# Sheet1.net
KiCad netlist of a schematic drawn in Altium Designer
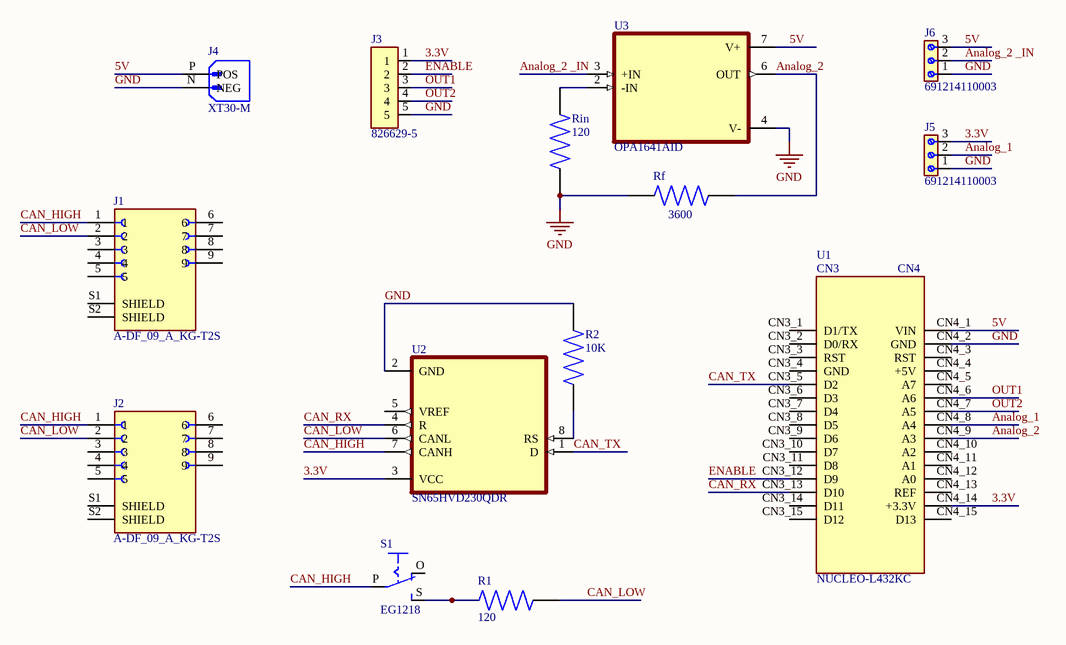
[diagram p0: Sheet1.SchDoc]

(export (version "E")
  (design (tool "Eeschema 10.0.6"))
  (components
    (comp (ref "J1")
      (value "A-DF_09_A_KG-T2S")
      (footprint "ASSMANN_A-DF_09_A_KG-T2S")
      (description "9 Position D-Sub Receptacle, Female Sockets Connector")
      (fields (field (name "MF") "Assmann WSW") (field (name "MP") "A-DF 09 A/KG-T2S"))
      (libsource (lib "A-DF_09_A_KG-T2S") (part "A-DF_09_A_KG-T2S"))
    )
    (comp (ref "J2")
      (value "A-DF_09_A_KG-T2S")
      (footprint "ASSMANN_A-DF_09_A_KG-T2S")
      (description "9 Position D-Sub Receptacle, Female Sockets Connector")
      (fields (field (name "MF") "Assmann WSW") (field (name "MP") "A-DF 09 A/KG-T2S"))
      (libsource (lib "A-DF_09_A_KG-T2S") (part "A-DF_09_A_KG-T2S"))
    )
    (comp (ref "J3")
      (value "826629-5")
      (footprint "TE_826629-5")
      (description "Board-To-Board Connector, AMPMODU MOD II Series, Through Hole, Header, 5, 2.54 mm")
      (fields (field (name "MF") "TE Connectivity"))
      (libsource (lib "826629-5") (part "826629-5"))
    )
    (comp (ref "J4")
      (value "XT30-M")
      (footprint "AMASS_XT60-M")
      (description "Plug; DC supply; XT60; male; PIN: 2; for cable; soldered; 30A; 500V")
      (fields (field (name "MP") "XT60-M") (field (name "MF") "AMASS"))
      (libsource (lib "XT30-M") (part "XT30-M"))
    )
    (comp (ref "J5")
      (value "691214110003")
      (footprint "691214110003")
      (description "PCB Terminal Block [WÃ¼rth Elektronik] 691214110003 PCB Terminal Block")
      (fields (field (name "MF") "Wurth Electronics"))
      (libsource (lib "691214110003") (part "691214110003"))
    )
    (comp (ref "J6")
      (value "691214110003")
      (footprint "691214110003")
      (description "PCB Terminal Block [WÃ¼rth Elektronik] 691214110003 PCB Terminal Block")
      (fields (field (name "MF") "Wurth Electronics"))
      (libsource (lib "691214110003") (part "691214110003"))
    )
    (comp (ref "R1")
      (value "120")
      (footprint "RESC3216X65N")
      (fields (field (name "MP") "KTR18EZPF9530"))
      (libsource (lib "KTR18EZPF9530") (part "KTR18EZPF9530"))
    )
    (comp (ref "R2")
      (value "10K")
      (footprint "RESC3216X65N")
      (fields (field (name "MP") "KTR18EZPF9530"))
      (libsource (lib "KTR18EZPF9530") (part "KTR18EZPF9530"))
    )
    (comp (ref "Rf")
      (value "3600")
      (footprint "RESC3216X65N")
      (fields (field (name "MP") "KTR18EZPF9530"))
      (libsource (lib "KTR18EZPF9530") (part "KTR18EZPF9530"))
    )
    (comp (ref "Rin")
      (value "120")
      (footprint "RESC3216X65N")
      (fields (field (name "MP") "KTR18EZPF9530"))
      (libsource (lib "KTR18EZPF9530") (part "KTR18EZPF9530"))
    )
    (comp (ref "S1") (value "EG1218") (footprint "EG1218:EG1218") (libsource (lib "EG1218") (part "EG1218")))
    (comp (ref "U1")
      (value "NUCLEO-L432KC")
      (footprint "MODULE_NUCLEO-L432KC")
      (description "STM32 Nucleo-32 development board with STM32L432KC MCU, supports Arduino connectivity")
      (libsource (lib "NUCLEO-L432KC") (part "NUCLEO-L432KC"))
    )
    (comp (ref "U2")
      (value "SN65HVD230QDR")
      (footprint "SOIC127P599X175-8N")
      (description "3.3-V CAN Transceiver with Standby Mode 8-SOIC -40 to 125")
      (fields (field (name "MF") "Texas Instruments"))
      (libsource (lib "SN65HVD230QDR") (part "SN65HVD230QDR"))
    )
    (comp (ref "U3")
      (value "OPA1641AID")
      (footprint "SOIC127P599X175-8N")
      (description "Single Sound-Plus High-Performance, JFET-Input Audio OpAmps 8-SOIC -40 to 85")
      (fields (field (name "MF") "Texas Instruments") (field (name "DIGI-KEY_PART_NUMBER") "296-48624-2-ND"))
      (libsource (lib "OPA1641AID") (part "OPA1641AID"))
    )
  )
  (nets
    (net (code "1") (name "/3.3V") (class "Default")
      (node (ref "J3") (pin "1") (pinfunction "1_1") (pintype "passive"))
      (node (ref "J5") (pin "3") (pinfunction "3_3") (pintype "passive"))
      (node (ref "U1") (pin "CN4_14") (pinfunction "+3.3V_CN4_14") (pintype "power_in"))
      (node (ref "U2") (pin "3") (pinfunction "VCC_3") (pintype "power_in"))
    )
    (net (code "2") (name "/5V") (class "Default")
      (node (ref "J4") (pin "P") (pinfunction "POS_P") (pintype "passive"))
      (node (ref "J6") (pin "3") (pinfunction "3_3") (pintype "passive"))
      (node (ref "U1") (pin "CN4_1") (pinfunction "VIN_CN4_1") (pintype "power_in"))
      (node (ref "U3") (pin "7") (pinfunction "V+_7") (pintype "power_in"))
    )
    (net (code "3") (name "/Analog_1") (class "Default")
      (node (ref "J5") (pin "2") (pinfunction "2_2") (pintype "passive"))
      (node (ref "U1") (pin "CN4_8") (pinfunction "A4_CN4_8") (pintype "passive"))
    )
    (net (code "4") (name "/Analog_2") (class "Default")
      (node (ref "Rf") (pin "1") (pinfunction "1_1") (pintype "passive"))
      (node (ref "U1") (pin "CN4_9") (pinfunction "A3_CN4_9") (pintype "passive"))
      (node (ref "U3") (pin "6") (pinfunction "OUT_6") (pintype "output"))
    )
    (net (code "5") (name "/Analog_2 _IN") (class "Default")
      (node (ref "J6") (pin "2") (pinfunction "2_2") (pintype "passive"))
      (node (ref "U3") (pin "3") (pinfunction "+IN_3") (pintype "input"))
    )
    (net (code "6") (name "/CAN_HIGH") (class "Default")
      (node (ref "J1") (pin "1") (pinfunction "1_1") (pintype "passive"))
      (node (ref "J2") (pin "1") (pinfunction "1_1") (pintype "passive"))
      (node (ref "S1") (pin "P") (pinfunction "P_P") (pintype "passive"))
      (node (ref "U2") (pin "7") (pinfunction "CANH_7") (pintype "output"))
    )
    (net (code "7") (name "/CAN_LOW") (class "Default")
      (node (ref "J1") (pin "2") (pinfunction "2_2") (pintype "passive"))
      (node (ref "J2") (pin "2") (pinfunction "2_2") (pintype "passive"))
      (node (ref "R1") (pin "2") (pinfunction "2_2") (pintype "passive"))
      (node (ref "U2") (pin "6") (pinfunction "CANL_6") (pintype "output"))
    )
    (net (code "8") (name "/CAN_RX") (class "Default")
      (node (ref "U1") (pin "CN3_13") (pinfunction "D10_CN3_13") (pintype "passive"))
      (node (ref "U2") (pin "4") (pinfunction "R_4") (pintype "output"))
    )
    (net (code "9") (name "/CAN_TX") (class "Default")
      (node (ref "U1") (pin "CN3_5") (pinfunction "D2_CN3_5") (pintype "power_in"))
      (node (ref "U2") (pin "1") (pinfunction "D_1") (pintype "input"))
    )
    (net (code "10") (name "/ENABLE") (class "Default")
      (node (ref "J3") (pin "2") (pinfunction "2_2") (pintype "passive"))
      (node (ref "U1") (pin "CN3_12") (pinfunction "D9_CN3_12") (pintype "power_in"))
    )
    (net (code "11") (name "/OUT1") (class "Default")
      (node (ref "J3") (pin "3") (pinfunction "3_3") (pintype "passive"))
      (node (ref "U1") (pin "CN4_6") (pinfunction "A6_CN4_6") (pintype "passive"))
    )
    (net (code "12") (name "/OUT2") (class "Default")
      (node (ref "J3") (pin "4") (pinfunction "4_4") (pintype "passive"))
      (node (ref "U1") (pin "CN4_7") (pinfunction "A5_CN4_7") (pintype "passive"))
    )
    (net (code "13") (name "GND") (class "Default")
      (node (ref "J3") (pin "5") (pinfunction "5_5") (pintype "passive"))
      (node (ref "J4") (pin "N") (pinfunction "NEG_N") (pintype "passive"))
      (node (ref "J5") (pin "1") (pinfunction "1_1") (pintype "passive"))
      (node (ref "J6") (pin "1") (pinfunction "1_1") (pintype "passive"))
      (node (ref "R2") (pin "2") (pinfunction "2_2") (pintype "passive"))
      (node (ref "Rf") (pin "2") (pinfunction "2_2") (pintype "passive"))
      (node (ref "Rin") (pin "1") (pinfunction "1_1") (pintype "passive"))
      (node (ref "U1") (pin "CN4_2") (pinfunction "GND_CN4_2") (pintype "power_in"))
      (node (ref "U2") (pin "2") (pinfunction "GND_2") (pintype "power_in"))
      (node (ref "U3") (pin "4") (pinfunction "V-_4") (pintype "power_in"))
    )
    (net (code "14") (name "Net-(R1-Pad1)") (class "Default")
      (node (ref "R1") (pin "1") (pinfunction "1_1") (pintype "passive"))
      (node (ref "S1") (pin "S") (pinfunction "S_S") (pintype "passive"))
    )
    (net (code "15") (name "Net-(U2-RS)") (class "Default")
      (node (ref "R2") (pin "1") (pinfunction "1_1") (pintype "passive"))
      (node (ref "U2") (pin "8") (pinfunction "RS_8") (pintype "input"))
    )
    (net (code "16") (name "Net-(U3--IN)") (class "Default")
      (node (ref "Rin") (pin "2") (pinfunction "2_2") (pintype "passive"))
      (node (ref "U3") (pin "2") (pinfunction "-IN_2") (pintype "input"))
    )
    (net (code "17") (name "unconnected-(J1-Pad3)") (class "Default")
      (node (ref "J1") (pin "3") (pinfunction "3_3") (pintype "passive"))
    )
    (net (code "18") (name "unconnected-(J1-Pad4)") (class "Default")
      (node (ref "J1") (pin "4") (pinfunction "4_4") (pintype "passive"))
    )
    (net (code "19") (name "unconnected-(J1-Pad5)") (class "Default")
      (node (ref "J1") (pin "5") (pinfunction "5_5") (pintype "passive"))
    )
    (net (code "20") (name "unconnected-(J1-Pad6)") (class "Default")
      (node (ref "J1") (pin "6") (pinfunction "6_6") (pintype "passive"))
    )
    (net (code "21") (name "unconnected-(J1-Pad7)") (class "Default")
      (node (ref "J1") (pin "7") (pinfunction "7_7") (pintype "passive"))
    )
    (net (code "22") (name "unconnected-(J1-Pad8)") (class "Default")
      (node (ref "J1") (pin "8") (pinfunction "8_8") (pintype "passive"))
    )
    (net (code "23") (name "unconnected-(J1-Pad9)") (class "Default")
      (node (ref "J1") (pin "9") (pinfunction "9_9") (pintype "passive"))
    )
    (net (code "24") (name "unconnected-(J1-SHIELD-PadS1)") (class "Default")
      (node (ref "J1") (pin "S1") (pinfunction "SHIELD_S1") (pintype "passive"))
    )
    (net (code "25") (name "unconnected-(J1-SHIELD-PadS2)") (class "Default")
      (node (ref "J1") (pin "S2") (pinfunction "SHIELD_S2") (pintype "passive"))
    )
    (net (code "26") (name "unconnected-(J2-Pad3)") (class "Default")
      (node (ref "J2") (pin "3") (pinfunction "3_3") (pintype "passive"))
    )
    (net (code "27") (name "unconnected-(J2-Pad4)") (class "Default")
      (node (ref "J2") (pin "4") (pinfunction "4_4") (pintype "passive"))
    )
    (net (code "28") (name "unconnected-(J2-Pad5)") (class "Default")
      (node (ref "J2") (pin "5") (pinfunction "5_5") (pintype "passive"))
    )
    (net (code "29") (name "unconnected-(J2-Pad6)") (class "Default")
      (node (ref "J2") (pin "6") (pinfunction "6_6") (pintype "passive"))
    )
    (net (code "30") (name "unconnected-(J2-Pad7)") (class "Default")
      (node (ref "J2") (pin "7") (pinfunction "7_7") (pintype "passive"))
    )
    (net (code "31") (name "unconnected-(J2-Pad8)") (class "Default")
      (node (ref "J2") (pin "8") (pinfunction "8_8") (pintype "passive"))
    )
    (net (code "32") (name "unconnected-(J2-Pad9)") (class "Default")
      (node (ref "J2") (pin "9") (pinfunction "9_9") (pintype "passive"))
    )
    (net (code "33") (name "unconnected-(J2-SHIELD-PadS1)") (class "Default")
      (node (ref "J2") (pin "S1") (pinfunction "SHIELD_S1") (pintype "passive"))
    )
    (net (code "34") (name "unconnected-(J2-SHIELD-PadS2)") (class "Default")
      (node (ref "J2") (pin "S2") (pinfunction "SHIELD_S2") (pintype "passive"))
    )
    (net (code "35") (name "unconnected-(S1-PadO)") (class "Default")
      (node (ref "S1") (pin "O") (pinfunction "O_O") (pintype "passive"))
    )
    (net (code "36") (name "unconnected-(U1-+5V-PadCN4_4)") (class "Default")
      (node (ref "U1") (pin "CN4_4") (pinfunction "+5V_CN4_4") (pintype "power_in"))
    )
    (net (code "37") (name "unconnected-(U1-A0-PadCN4_12)") (class "Default")
      (node (ref "U1") (pin "CN4_12") (pinfunction "A0_CN4_12") (pintype "passive"))
    )
    (net (code "38") (name "unconnected-(U1-A1-PadCN4_11)") (class "Default")
      (node (ref "U1") (pin "CN4_11") (pinfunction "A1_CN4_11") (pintype "passive"))
    )
    (net (code "39") (name "unconnected-(U1-A2-PadCN4_10)") (class "Default")
      (node (ref "U1") (pin "CN4_10") (pinfunction "A2_CN4_10") (pintype "passive"))
    )
    (net (code "40") (name "unconnected-(U1-A7-PadCN4_5)") (class "Default")
      (node (ref "U1") (pin "CN4_5") (pinfunction "A7_CN4_5") (pintype "passive"))
    )
    (net (code "41") (name "unconnected-(U1-D0{slash}RX-PadCN3_2)") (class "Default")
      (node (ref "U1") (pin "CN3_2") (pinfunction "D0/RX_CN3_2") (pintype "power_in"))
    )
    (net (code "42") (name "unconnected-(U1-D1{slash}TX-PadCN3_1)") (class "Default")
      (node (ref "U1") (pin "CN3_1") (pinfunction "D1/TX_CN3_1") (pintype "power_in"))
    )
    (net (code "43") (name "unconnected-(U1-D3-PadCN3_6)") (class "Default")
      (node (ref "U1") (pin "CN3_6") (pinfunction "D3_CN3_6") (pintype "power_in"))
    )
    (net (code "44") (name "unconnected-(U1-D4-PadCN3_7)") (class "Default")
      (node (ref "U1") (pin "CN3_7") (pinfunction "D4_CN3_7") (pintype "power_in"))
    )
    (net (code "45") (name "unconnected-(U1-D5-PadCN3_8)") (class "Default")
      (node (ref "U1") (pin "CN3_8") (pinfunction "D5_CN3_8") (pintype "power_in"))
    )
    (net (code "46") (name "unconnected-(U1-D6-PadCN3_9)") (class "Default")
      (node (ref "U1") (pin "CN3_9") (pinfunction "D6_CN3_9") (pintype "power_in"))
    )
    (net (code "47") (name "unconnected-(U1-D7-PadCN3_10)") (class "Default")
      (node (ref "U1") (pin "CN3_10") (pinfunction "D7_CN3_10") (pintype "power_in"))
    )
    (net (code "48") (name "unconnected-(U1-D8-PadCN3_11)") (class "Default")
      (node (ref "U1") (pin "CN3_11") (pinfunction "D8_CN3_11") (pintype "power_in"))
    )
    (net (code "49") (name "unconnected-(U1-D11-PadCN3_14)") (class "Default")
      (node (ref "U1") (pin "CN3_14") (pinfunction "D11_CN3_14") (pintype "power_in"))
    )
    (net (code "50") (name "unconnected-(U1-D12-PadCN3_15)") (class "Default")
      (node (ref "U1") (pin "CN3_15") (pinfunction "D12_CN3_15") (pintype "power_in"))
    )
    (net (code "51") (name "unconnected-(U1-D13-PadCN4_15)") (class "Default")
      (node (ref "U1") (pin "CN4_15") (pinfunction "D13_CN4_15") (pintype "power_in"))
    )
    (net (code "52") (name "unconnected-(U1-GND-PadCN3_4)") (class "Default")
      (node (ref "U1") (pin "CN3_4") (pinfunction "GND_CN3_4") (pintype "power_in"))
    )
    (net (code "53") (name "unconnected-(U1-REF-PadCN4_13)") (class "Default")
      (node (ref "U1") (pin "CN4_13") (pinfunction "REF_CN4_13") (pintype "passive"))
    )
    (net (code "54") (name "unconnected-(U1-RST-PadCN3_3)") (class "Default")
      (node (ref "U1") (pin "CN3_3") (pinfunction "RST_CN3_3") (pintype "power_in"))
    )
    (net (code "55") (name "unconnected-(U1-RST-PadCN4_3)") (class "Default")
      (node (ref "U1") (pin "CN4_3") (pinfunction "RST_CN4_3") (pintype "passive"))
    )
    (net (code "56") (name "unconnected-(U2-VREF-Pad5)") (class "Default")
      (node (ref "U2") (pin "5") (pinfunction "VREF_5") (pintype "output"))
    )
  )
)
